# display1.net
KiCad netlist of a schematic drawn in EAGLE
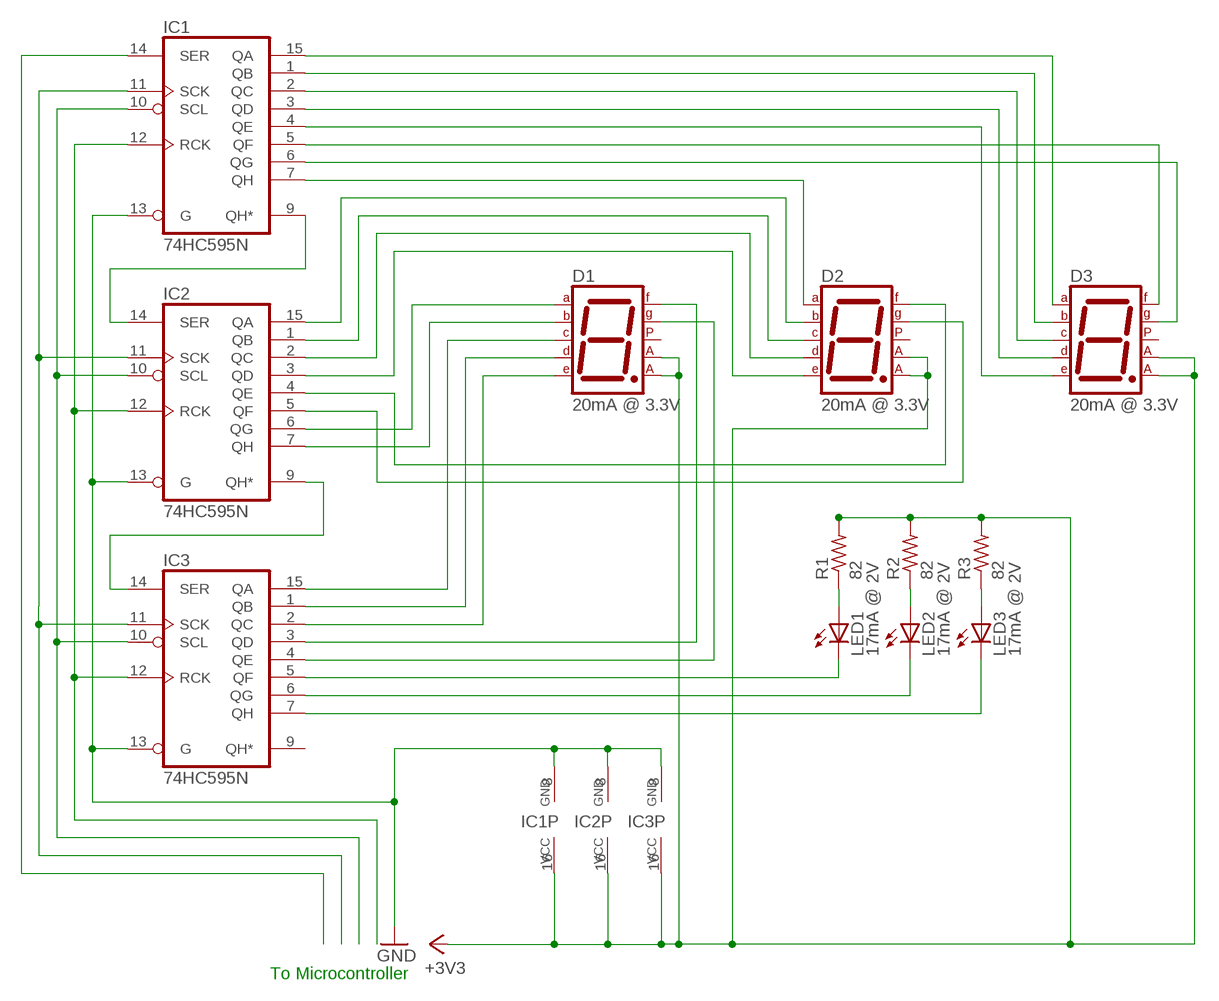
[diagram p0: schematic, sheet 1]

(export (version "E")
  (design (tool "Eeschema 10.0.6"))
  (components
    (comp (ref "D1")
      (value "20mA @ 3.3V")
      (footprint "eagle-import:7SEG-13")
      (libsource (lib "eagle-import") (part "7SEG-CA"))
    )
    (comp (ref "D2")
      (value "20mA @ 3.3V")
      (footprint "eagle-import:7SEG-13")
      (libsource (lib "eagle-import") (part "7SEG-CA"))
    )
    (comp (ref "D3")
      (value "20mA @ 3.3V")
      (footprint "eagle-import:7SEG-13")
      (libsource (lib "eagle-import") (part "7SEG-CA"))
    )
    (comp (ref "IC1")
      (value "74HC595N")
      (footprint "eagle-import:DIL16")
      (libsource (lib "eagle-import") (part "74595NHC"))
    )
    (comp (ref "IC2")
      (value "74HC595N")
      (footprint "eagle-import:DIL16")
      (libsource (lib "eagle-import") (part "74595NHC"))
    )
    (comp (ref "IC3")
      (value "74HC595N")
      (footprint "eagle-import:DIL16")
      (libsource (lib "eagle-import") (part "74595NHC"))
    )
    (comp (ref "LED1")
      (value "17mA @ 2V")
      (footprint "eagle-import:LED3MM")
      (libsource (lib "eagle-import") (part "LED3MM"))
    )
    (comp (ref "LED2")
      (value "17mA @ 2V")
      (footprint "eagle-import:LED3MM")
      (libsource (lib "eagle-import") (part "LED3MM"))
    )
    (comp (ref "LED3")
      (value "17mA @ 2V")
      (footprint "eagle-import:LED3MM")
      (libsource (lib "eagle-import") (part "LED3MM"))
    )
    (comp (ref "R1")
      (value "82")
      (footprint "eagle-import:0207_10")
      (libsource (lib "eagle-import") (part "R-US_0207/10"))
    )
    (comp (ref "R2")
      (value "82")
      (footprint "eagle-import:0207_10")
      (libsource (lib "eagle-import") (part "R-US_0207/10"))
    )
    (comp (ref "R3")
      (value "82")
      (footprint "eagle-import:0207_10")
      (libsource (lib "eagle-import") (part "R-US_0207/10"))
    )
  )
  (nets
    (net (code "1") (name "+3V3") (class "Default")
      (node (ref "D1") (pin "3") (pinfunction "CA1_3") (pintype "passive"))
      (node (ref "D1") (pin "8") (pinfunction "CA2_8") (pintype "passive"))
      (node (ref "D2") (pin "3") (pinfunction "CA1_3") (pintype "passive"))
      (node (ref "D2") (pin "8") (pinfunction "CA2_8") (pintype "passive"))
      (node (ref "D3") (pin "3") (pinfunction "CA1_3") (pintype "passive"))
      (node (ref "D3") (pin "8") (pinfunction "CA2_8") (pintype "passive"))
      (node (ref "IC1") (pin "16") (pinfunction "VCC_16") (pintype "power_in"))
      (node (ref "IC2") (pin "16") (pinfunction "VCC_16") (pintype "power_in"))
      (node (ref "IC3") (pin "16") (pinfunction "VCC_16") (pintype "power_in"))
      (node (ref "R1") (pin "2") (pinfunction "2_2") (pintype "passive"))
      (node (ref "R2") (pin "2") (pinfunction "2_2") (pintype "passive"))
      (node (ref "R3") (pin "2") (pinfunction "2_2") (pintype "passive"))
    )
    (net (code "2") (name "GND") (class "Default")
      (node (ref "IC1") (pin "13") (pinfunction "G_13") (pintype "input"))
      (node (ref "IC1") (pin "8") (pinfunction "GND_8") (pintype "power_in"))
      (node (ref "IC2") (pin "13") (pinfunction "G_13") (pintype "input"))
      (node (ref "IC2") (pin "8") (pinfunction "GND_8") (pintype "power_in"))
      (node (ref "IC3") (pin "13") (pinfunction "G_13") (pintype "input"))
      (node (ref "IC3") (pin "8") (pinfunction "GND_8") (pintype "power_in"))
    )
    (net (code "3") (name "Net-(D1-A)") (class "Default")
      (node (ref "D1") (pin "7") (pinfunction "A_7") (pintype "passive"))
      (node (ref "IC2") (pin "6") (pinfunction "QG_6") (pintype "tri_state"))
    )
    (net (code "4") (name "Net-(D1-B)") (class "Default")
      (node (ref "D1") (pin "6") (pinfunction "B_6") (pintype "passive"))
      (node (ref "IC2") (pin "7") (pinfunction "QH_7") (pintype "tri_state"))
    )
    (net (code "5") (name "Net-(D1-C)") (class "Default")
      (node (ref "D1") (pin "4") (pinfunction "C_4") (pintype "passive"))
      (node (ref "IC3") (pin "15") (pinfunction "QA_15") (pintype "tri_state"))
    )
    (net (code "6") (name "Net-(D1-D)") (class "Default")
      (node (ref "D1") (pin "2") (pinfunction "D_2") (pintype "passive"))
      (node (ref "IC3") (pin "1") (pinfunction "QB_1") (pintype "tri_state"))
    )
    (net (code "7") (name "Net-(D1-E)") (class "Default")
      (node (ref "D1") (pin "1") (pinfunction "E_1") (pintype "passive"))
      (node (ref "IC3") (pin "2") (pinfunction "QC_2") (pintype "tri_state"))
    )
    (net (code "8") (name "Net-(D1-F)") (class "Default")
      (node (ref "D1") (pin "9") (pinfunction "F_9") (pintype "passive"))
      (node (ref "IC3") (pin "3") (pinfunction "QD_3") (pintype "tri_state"))
    )
    (net (code "9") (name "Net-(D1-G)") (class "Default")
      (node (ref "D1") (pin "10") (pinfunction "G_10") (pintype "passive"))
      (node (ref "IC3") (pin "4") (pinfunction "QE_4") (pintype "tri_state"))
    )
    (net (code "10") (name "Net-(D2-A)") (class "Default")
      (node (ref "D2") (pin "7") (pinfunction "A_7") (pintype "passive"))
      (node (ref "IC1") (pin "7") (pinfunction "QH_7") (pintype "tri_state"))
    )
    (net (code "11") (name "Net-(D2-B)") (class "Default")
      (node (ref "D2") (pin "6") (pinfunction "B_6") (pintype "passive"))
      (node (ref "IC2") (pin "15") (pinfunction "QA_15") (pintype "tri_state"))
    )
    (net (code "12") (name "Net-(D2-C)") (class "Default")
      (node (ref "D2") (pin "4") (pinfunction "C_4") (pintype "passive"))
      (node (ref "IC2") (pin "1") (pinfunction "QB_1") (pintype "tri_state"))
    )
    (net (code "13") (name "Net-(D2-D)") (class "Default")
      (node (ref "D2") (pin "2") (pinfunction "D_2") (pintype "passive"))
      (node (ref "IC2") (pin "2") (pinfunction "QC_2") (pintype "tri_state"))
    )
    (net (code "14") (name "Net-(D2-E)") (class "Default")
      (node (ref "D2") (pin "1") (pinfunction "E_1") (pintype "passive"))
      (node (ref "IC2") (pin "3") (pinfunction "QD_3") (pintype "tri_state"))
    )
    (net (code "15") (name "Net-(D2-F)") (class "Default")
      (node (ref "D2") (pin "9") (pinfunction "F_9") (pintype "passive"))
      (node (ref "IC2") (pin "4") (pinfunction "QE_4") (pintype "tri_state"))
    )
    (net (code "16") (name "Net-(D2-G)") (class "Default")
      (node (ref "D2") (pin "10") (pinfunction "G_10") (pintype "passive"))
      (node (ref "IC2") (pin "5") (pinfunction "QF_5") (pintype "tri_state"))
    )
    (net (code "17") (name "Net-(D3-A)") (class "Default")
      (node (ref "D3") (pin "7") (pinfunction "A_7") (pintype "passive"))
      (node (ref "IC1") (pin "15") (pinfunction "QA_15") (pintype "tri_state"))
    )
    (net (code "18") (name "Net-(D3-B)") (class "Default")
      (node (ref "D3") (pin "6") (pinfunction "B_6") (pintype "passive"))
      (node (ref "IC1") (pin "1") (pinfunction "QB_1") (pintype "tri_state"))
    )
    (net (code "19") (name "Net-(D3-C)") (class "Default")
      (node (ref "D3") (pin "4") (pinfunction "C_4") (pintype "passive"))
      (node (ref "IC1") (pin "2") (pinfunction "QC_2") (pintype "tri_state"))
    )
    (net (code "20") (name "Net-(D3-D)") (class "Default")
      (node (ref "D3") (pin "2") (pinfunction "D_2") (pintype "passive"))
      (node (ref "IC1") (pin "3") (pinfunction "QD_3") (pintype "tri_state"))
    )
    (net (code "21") (name "Net-(D3-E)") (class "Default")
      (node (ref "D3") (pin "1") (pinfunction "E_1") (pintype "passive"))
      (node (ref "IC1") (pin "4") (pinfunction "QE_4") (pintype "tri_state"))
    )
    (net (code "22") (name "Net-(D3-F)") (class "Default")
      (node (ref "D3") (pin "9") (pinfunction "F_9") (pintype "passive"))
      (node (ref "IC1") (pin "5") (pinfunction "QF_5") (pintype "tri_state"))
    )
    (net (code "23") (name "Net-(D3-G)") (class "Default")
      (node (ref "D3") (pin "10") (pinfunction "G_10") (pintype "passive"))
      (node (ref "IC1") (pin "6") (pinfunction "QG_6") (pintype "tri_state"))
    )
    (net (code "24") (name "Net-(IC1A-QH*)") (class "Default")
      (node (ref "IC1") (pin "9") (pinfunction "QH*_9") (pintype "tri_state"))
      (node (ref "IC2") (pin "14") (pinfunction "SER_14") (pintype "input"))
    )
    (net (code "25") (name "Net-(IC1A-RCK)") (class "Default")
      (node (ref "IC1") (pin "12") (pinfunction "RCK_12") (pintype "input"))
      (node (ref "IC2") (pin "12") (pinfunction "RCK_12") (pintype "input"))
      (node (ref "IC3") (pin "12") (pinfunction "RCK_12") (pintype "input"))
    )
    (net (code "26") (name "Net-(IC1A-SCK)") (class "Default")
      (node (ref "IC1") (pin "11") (pinfunction "SCK_11") (pintype "input"))
      (node (ref "IC2") (pin "11") (pinfunction "SCK_11") (pintype "input"))
      (node (ref "IC3") (pin "11") (pinfunction "SCK_11") (pintype "input"))
    )
    (net (code "27") (name "Net-(IC1A-SCL)") (class "Default")
      (node (ref "IC1") (pin "10") (pinfunction "SCL_10") (pintype "input"))
      (node (ref "IC2") (pin "10") (pinfunction "SCL_10") (pintype "input"))
      (node (ref "IC3") (pin "10") (pinfunction "SCL_10") (pintype "input"))
    )
    (net (code "28") (name "Net-(IC2A-QH*)") (class "Default")
      (node (ref "IC2") (pin "9") (pinfunction "QH*_9") (pintype "tri_state"))
      (node (ref "IC3") (pin "14") (pinfunction "SER_14") (pintype "input"))
    )
    (net (code "29") (name "Net-(IC3A-QF)") (class "Default")
      (node (ref "IC3") (pin "5") (pinfunction "QF_5") (pintype "tri_state"))
      (node (ref "LED1") (pin "K") (pinfunction "C_K") (pintype "passive"))
    )
    (net (code "30") (name "Net-(IC3A-QG)") (class "Default")
      (node (ref "IC3") (pin "6") (pinfunction "QG_6") (pintype "tri_state"))
      (node (ref "LED2") (pin "K") (pinfunction "C_K") (pintype "passive"))
    )
    (net (code "31") (name "Net-(IC3A-QH)") (class "Default")
      (node (ref "IC3") (pin "7") (pinfunction "QH_7") (pintype "tri_state"))
      (node (ref "LED3") (pin "K") (pinfunction "C_K") (pintype "passive"))
    )
    (net (code "32") (name "Net-(LED1-PadA)") (class "Default")
      (node (ref "LED1") (pin "A") (pinfunction "A_A") (pintype "passive"))
      (node (ref "R1") (pin "1") (pinfunction "1_1") (pintype "passive"))
    )
    (net (code "33") (name "Net-(LED2-PadA)") (class "Default")
      (node (ref "LED2") (pin "A") (pinfunction "A_A") (pintype "passive"))
      (node (ref "R2") (pin "1") (pinfunction "1_1") (pintype "passive"))
    )
    (net (code "34") (name "Net-(LED3-PadA)") (class "Default")
      (node (ref "LED3") (pin "A") (pinfunction "A_A") (pintype "passive"))
      (node (ref "R3") (pin "1") (pinfunction "1_1") (pintype "passive"))
    )
    (net (code "35") (name "unconnected-(D1-DP-Pad5)") (class "Default")
      (node (ref "D1") (pin "5") (pinfunction "DP_5") (pintype "passive"))
    )
    (net (code "36") (name "unconnected-(D2-DP-Pad5)") (class "Default")
      (node (ref "D2") (pin "5") (pinfunction "DP_5") (pintype "passive"))
    )
    (net (code "37") (name "unconnected-(D3-DP-Pad5)") (class "Default")
      (node (ref "D3") (pin "5") (pinfunction "DP_5") (pintype "passive"))
    )
    (net (code "38") (name "unconnected-(IC1A-SER-Pad14)") (class "Default")
      (node (ref "IC1") (pin "14") (pinfunction "SER_14") (pintype "input"))
    )
    (net (code "39") (name "unconnected-(IC3A-QH*-Pad9)") (class "Default")
      (node (ref "IC3") (pin "9") (pinfunction "QH*_9") (pintype "tri_state"))
    )
  )
)
